# Lora_Node.net
KiCad netlist of a schematic drawn in EAGLE
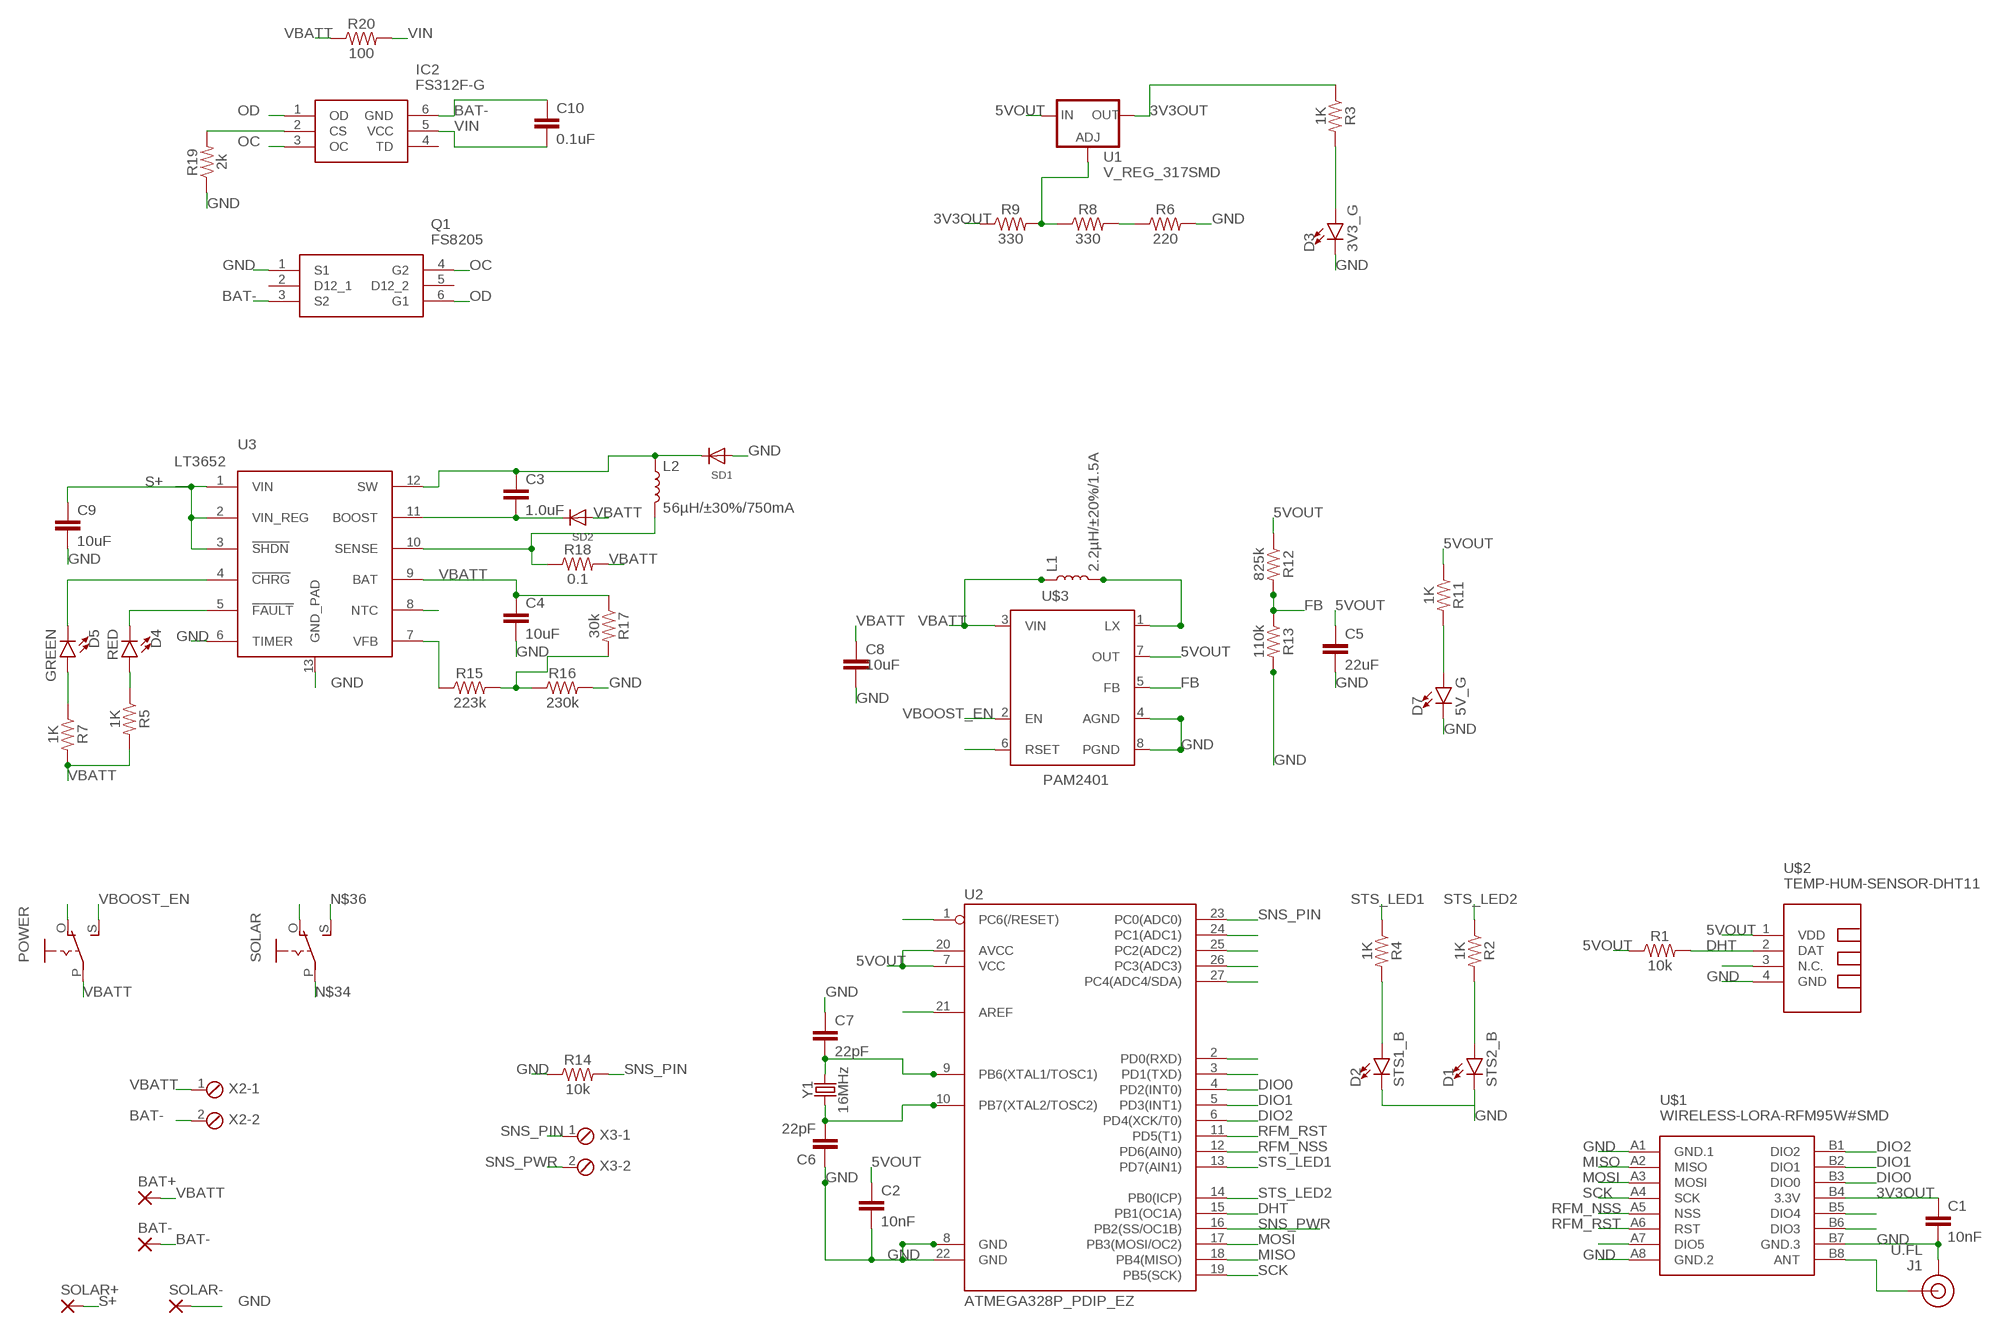
[diagram p0: schematic, sheet 1]

(export (version "E")
  (design (tool "Eeschema 10.0.6"))
  (components
    (comp (ref "BAT+")
      (value "SMD5")
      (footprint "eagle-import:SMD2,54-5,08")
      (libsource (lib "eagle-import") (part "SMD5"))
    )
    (comp (ref "BAT-")
      (value "SMD5")
      (footprint "eagle-import:SMD2,54-5,08")
      (libsource (lib "eagle-import") (part "SMD5"))
    )
    (comp (ref "C1")
      (value "10nF")
      (footprint "eagle-import:0603")
      (libsource (lib "eagle-import") (part "10NF-0603-50V-10%"))
    )
    (comp (ref "C2")
      (value "10nF")
      (footprint "eagle-import:0603")
      (libsource (lib "eagle-import") (part "10NF-0603-50V-10%"))
    )
    (comp (ref "C3")
      (value "1.0uF")
      (footprint "eagle-import:0805")
      (libsource (lib "eagle-import") (part "1.0UF-0805-25V-(+80/-20%)"))
    )
    (comp (ref "C4")
      (value "10uF")
      (footprint "eagle-import:0805")
      (libsource (lib "eagle-import") (part "10UF-0805-10V-10%"))
    )
    (comp (ref "C5")
      (value "22uF")
      (footprint "eagle-import:0805")
      (libsource (lib "eagle-import") (part "22UF-0805-6.3V-20%"))
    )
    (comp (ref "C6")
      (value "22pF")
      (footprint "eagle-import:0603")
      (libsource (lib "eagle-import") (part "22PF-0603-50V-5%"))
    )
    (comp (ref "C7")
      (value "22pF")
      (footprint "eagle-import:0603")
      (libsource (lib "eagle-import") (part "22PF-0603-50V-5%"))
    )
    (comp (ref "C8")
      (value "10uF")
      (footprint "eagle-import:0805")
      (libsource (lib "eagle-import") (part "10UF-0805-10V-10%"))
    )
    (comp (ref "C9")
      (value "10uF")
      (footprint "eagle-import:1210")
      (libsource (lib "eagle-import") (part "10UF-1210-50V-20%"))
    )
    (comp (ref "C10")
      (value "0.1uF")
      (footprint "eagle-import:0603")
      (libsource (lib "eagle-import") (part "0.1UF-0603-25V-5%"))
    )
    (comp (ref "D1")
      (value "STS2_B")
      (footprint "eagle-import:LED-1206")
      (libsource (lib "eagle-import") (part "LED-BLUE1206"))
    )
    (comp (ref "D2")
      (value "STS1_B")
      (footprint "eagle-import:LED-1206")
      (libsource (lib "eagle-import") (part "LED-BLUE1206"))
    )
    (comp (ref "D3")
      (value "3V3_G")
      (footprint "eagle-import:LED-0603")
      (libsource (lib "eagle-import") (part "LED-GREEN0603"))
    )
    (comp (ref "D4")
      (value "RED")
      (footprint "eagle-import:LED-0603")
      (libsource (lib "eagle-import") (part "LED-RED0603"))
    )
    (comp (ref "D5")
      (value "GREEN")
      (footprint "eagle-import:LED-0603")
      (libsource (lib "eagle-import") (part "LED-GREEN0603"))
    )
    (comp (ref "D7")
      (value "5V_G")
      (footprint "eagle-import:LED-0603")
      (libsource (lib "eagle-import") (part "LED-GREEN0603"))
    )
    (comp (ref "IC2")
      (value "FS312F-G")
      (footprint "eagle-import:SOT95P280X145-6N")
      (libsource (lib "eagle-import") (part "FS312F-G"))
    )
    (comp (ref "J1")
      (value "U.FL")
      (footprint "eagle-import:U.FL")
      (libsource (lib "eagle-import") (part "U.FL2PIN"))
    )
    (comp (ref "L1")
      (value "2.2µH/±20%/1.5A")
      (footprint "eagle-import:INDUCTOR_2.2UH")
      (libsource (lib "eagle-import") (part "INDUCTOR-VLF4012AT-2.2UH"))
    )
    (comp (ref "L2")
      (value "56µH/±30%/750mA")
      (footprint "eagle-import:CR54")
      (libsource (lib "eagle-import") (part "INDUCTOR-CR54-47UH"))
    )
    (comp (ref "POWER")
      (value "EG1218S")
      (footprint "eagle-import:EG1218")
      (libsource (lib "eagle-import") (part "EG1218S"))
    )
    (comp (ref "Q1")
      (value "FS8205")
      (footprint "eagle-import:FS8205")
      (libsource (lib "eagle-import") (part "FS8205"))
    )
    (comp (ref "R1")
      (value "10k")
      (footprint "eagle-import:0603")
      (libsource (lib "eagle-import") (part "10KOHM-0603-1/10W-1%"))
    )
    (comp (ref "R2")
      (value "1K")
      (footprint "eagle-import:0603")
      (libsource (lib "eagle-import") (part "220OHM-0603-1/10W-1%"))
    )
    (comp (ref "R3")
      (value "1K")
      (footprint "eagle-import:0603")
      (libsource (lib "eagle-import") (part "220OHM-0603-1/10W-1%"))
    )
    (comp (ref "R4")
      (value "1K")
      (footprint "eagle-import:0603")
      (libsource (lib "eagle-import") (part "220OHM-0603-1/10W-1%"))
    )
    (comp (ref "R5")
      (value "1K")
      (footprint "eagle-import:0603")
      (libsource (lib "eagle-import") (part "220OHM-0603-1/10W-1%"))
    )
    (comp (ref "R6")
      (value "220")
      (footprint "eagle-import:0603")
      (libsource (lib "eagle-import") (part "220OHM-0603-1/10W-1%"))
    )
    (comp (ref "R7")
      (value "1K")
      (footprint "eagle-import:0603")
      (libsource (lib "eagle-import") (part "220OHM-0603-1/10W-1%"))
    )
    (comp (ref "R8")
      (value "330")
      (footprint "eagle-import:0603")
      (libsource (lib "eagle-import") (part "330OHM-0603-1/10W-1%"))
    )
    (comp (ref "R9")
      (value "330")
      (footprint "eagle-import:0603")
      (libsource (lib "eagle-import") (part "330OHM-0603-1/10W-1%"))
    )
    (comp (ref "R11")
      (value "1K")
      (footprint "eagle-import:0603")
      (libsource (lib "eagle-import") (part "220OHM-0603-1/10W-1%"))
    )
    (comp (ref "R12")
      (value "825k")
      (footprint "eagle-import:0603")
      (libsource (lib "eagle-import") (part "820KOHM-0603-1/10W-1%"))
    )
    (comp (ref "R13")
      (value "110k")
      (footprint "eagle-import:0603")
      (libsource (lib "eagle-import") (part "100KOHM-0603-1/10W-1%"))
    )
    (comp (ref "R14")
      (value "10k")
      (footprint "eagle-import:0603")
      (libsource (lib "eagle-import") (part "10KOHM-0603-1/10W-1%"))
    )
    (comp (ref "R15")
      (value "223k")
      (footprint "eagle-import:0603")
      (libsource (lib "eagle-import") (part "220KOHM-0603-1/10W-1%"))
    )
    (comp (ref "R16")
      (value "230k")
      (footprint "eagle-import:0603")
      (libsource (lib "eagle-import") (part "220KOHM-0603-1/10W-1%"))
    )
    (comp (ref "R17")
      (value "30k")
      (footprint "eagle-import:0603")
      (libsource (lib "eagle-import") (part "30.1KOHM-0603-1/10W-1%"))
    )
    (comp (ref "R18")
      (value "0.1")
      (footprint "eagle-import:1210")
      (libsource (lib "eagle-import") (part "0.1OHM-1210-1/2W-1%"))
    )
    (comp (ref "R19")
      (value "2k")
      (footprint "eagle-import:0603")
      (libsource (lib "eagle-import") (part "220KOHM-0603-1/10W-1%"))
    )
    (comp (ref "R20")
      (value "100")
      (footprint "eagle-import:0603")
      (libsource (lib "eagle-import") (part "100OHM-0603-1/4W-5%"))
    )
    (comp (ref "SD1")
      (value "DIODESMA")
      (footprint "eagle-import:SMADIODE")
      (libsource (lib "eagle-import") (part "DIODESMA"))
    )
    (comp (ref "SD2")
      (value "DIODESMA")
      (footprint "eagle-import:SMADIODE")
      (libsource (lib "eagle-import") (part "DIODESMA"))
    )
    (comp (ref "SOLAR")
      (value "EG1218S")
      (footprint "eagle-import:EG1218")
      (libsource (lib "eagle-import") (part "EG1218S"))
    )
    (comp (ref "SOLAR+")
      (value "SMD5")
      (footprint "eagle-import:SMD2,54-5,08")
      (libsource (lib "eagle-import") (part "SMD5"))
    )
    (comp (ref "SOLAR-")
      (value "SMD5")
      (footprint "eagle-import:SMD2,54-5,08")
      (libsource (lib "eagle-import") (part "SMD5"))
    )
    (comp (ref "U$1")
      (value "WIRELESS-LORA-RFM95W#SMD")
      (footprint "eagle-import:WIRELESS-LORA-RFM95W#SMD")
      (libsource (lib "eagle-import") (part "WIRELESS-LORA-RFM95W#SMD"))
    )
    (comp (ref "U$2")
      (value "TEMP-HUM-SENSOR-DHT11")
      (footprint "eagle-import:TEMP-HUM-SENSOR-DHT11")
      (libsource (lib "eagle-import") (part "TEMP-HUM-SENSOR-DHT11"))
    )
    (comp (ref "U$3")
      (value "PAM2401")
      (footprint "eagle-import:MSOP8")
      (libsource (lib "eagle-import") (part "PAM2401"))
    )
    (comp (ref "U1")
      (value "V_REG_317SMD")
      (footprint "eagle-import:SOT223")
      (libsource (lib "eagle-import") (part "V_REG_317SMD"))
    )
    (comp (ref "U2")
      (value "ATMEGA328P_PDIP_EZ")
      (footprint "eagle-import:DIP28-SIMON-KIT")
      (libsource (lib "eagle-import") (part "ATMEGA328P_PDIP_EZ"))
    )
    (comp (ref "U3")
      (value "LT3652")
      (footprint "eagle-import:MSOP-12_GND")
      (libsource (lib "eagle-import") (part "LT3652"))
    )
    (comp (ref "X2")
      (value "MPT2")
      (footprint "eagle-import:2POL254")
      (libsource (lib "eagle-import") (part "MPT2"))
    )
    (comp (ref "X3")
      (value "MPT2")
      (footprint "eagle-import:2POL254")
      (libsource (lib "eagle-import") (part "MPT2"))
    )
    (comp (ref "Y1")
      (value "16MHz")
      (footprint "eagle-import:HC49US")
      (libsource (lib "eagle-import") (part "CRYSTAL-16MHZPTH-HC49US"))
    )
  )
  (nets
    (net (code "1") (name "/3V3OUT") (class "Default")
      (node (ref "C1") (pin "1") (pinfunction "1_1") (pintype "passive"))
      (node (ref "R3") (pin "1") (pinfunction "1_1") (pintype "passive"))
      (node (ref "R9") (pin "1") (pinfunction "1_1") (pintype "passive"))
      (node (ref "U$1") (pin "B4") (pinfunction "3.3V_B4") (pintype "power_in"))
      (node (ref "U1") (pin "2") (pinfunction "OUT_2") (pintype "output"))
    )
    (net (code "2") (name "/5VOUT") (class "Default")
      (node (ref "C2") (pin "1") (pinfunction "1_1") (pintype "passive"))
      (node (ref "C5") (pin "1") (pinfunction "1_1") (pintype "passive"))
      (node (ref "R1") (pin "1") (pinfunction "1_1") (pintype "passive"))
      (node (ref "R11") (pin "1") (pinfunction "1_1") (pintype "passive"))
      (node (ref "R12") (pin "1") (pinfunction "1_1") (pintype "passive"))
      (node (ref "U$2") (pin "1") (pinfunction "VDD_1") (pintype "power_in"))
      (node (ref "U$3") (pin "7") (pinfunction "OUT_7") (pintype "bidirectional"))
      (node (ref "U1") (pin "3") (pinfunction "IN_3") (pintype "input"))
      (node (ref "U2") (pin "20") (pinfunction "AVCC_20") (pintype "bidirectional"))
      (node (ref "U2") (pin "7") (pinfunction "VCC_7") (pintype "bidirectional"))
    )
    (net (code "3") (name "/BAT-") (class "Default")
      (node (ref "BAT-") (pin "1") (pinfunction "P_1") (pintype "passive"))
      (node (ref "C10") (pin "1") (pinfunction "1_1") (pintype "passive"))
      (node (ref "IC2") (pin "6") (pinfunction "GND_6") (pintype "bidirectional"))
      (node (ref "Q1") (pin "3") (pinfunction "S2_3") (pintype "bidirectional"))
      (node (ref "X2") (pin "2") (pinfunction "1_2") (pintype "passive"))
    )
    (net (code "4") (name "/DHT") (class "Default")
      (node (ref "R1") (pin "2") (pinfunction "2_2") (pintype "passive"))
      (node (ref "U$2") (pin "2") (pinfunction "DAT_2") (pintype "bidirectional"))
      (node (ref "U2") (pin "15") (pinfunction "PB1(OC1A)_15") (pintype "bidirectional"))
    )
    (net (code "5") (name "/DIO0") (class "Default")
      (node (ref "U$1") (pin "B3") (pinfunction "DIO0_B3") (pintype "bidirectional"))
      (node (ref "U2") (pin "4") (pinfunction "PD2(INT0)_4") (pintype "bidirectional"))
    )
    (net (code "6") (name "/DIO1") (class "Default")
      (node (ref "U$1") (pin "B2") (pinfunction "DIO1_B2") (pintype "bidirectional"))
      (node (ref "U2") (pin "5") (pinfunction "PD3(INT1)_5") (pintype "bidirectional"))
    )
    (net (code "7") (name "/DIO2") (class "Default")
      (node (ref "U$1") (pin "B1") (pinfunction "DIO2_B1") (pintype "bidirectional"))
      (node (ref "U2") (pin "6") (pinfunction "PD4(XCK/T0)_6") (pintype "bidirectional"))
    )
    (net (code "8") (name "/FB") (class "Default")
      (node (ref "R12") (pin "2") (pinfunction "2_2") (pintype "passive"))
      (node (ref "R13") (pin "1") (pinfunction "1_1") (pintype "passive"))
      (node (ref "U$3") (pin "5") (pinfunction "FB_5") (pintype "bidirectional"))
    )
    (net (code "9") (name "/GND") (class "Default")
      (node (ref "C1") (pin "2") (pinfunction "2_2") (pintype "passive"))
      (node (ref "C2") (pin "2") (pinfunction "2_2") (pintype "passive"))
      (node (ref "C4") (pin "2") (pinfunction "2_2") (pintype "passive"))
      (node (ref "C5") (pin "2") (pinfunction "2_2") (pintype "passive"))
      (node (ref "C6") (pin "1") (pinfunction "1_1") (pintype "passive"))
      (node (ref "C7") (pin "1") (pinfunction "1_1") (pintype "passive"))
      (node (ref "C8") (pin "2") (pinfunction "2_2") (pintype "passive"))
      (node (ref "C9") (pin "2") (pinfunction "2_2") (pintype "passive"))
      (node (ref "D1") (pin "C") (pinfunction "C_C") (pintype "passive"))
      (node (ref "D2") (pin "C") (pinfunction "C_C") (pintype "passive"))
      (node (ref "D3") (pin "C") (pinfunction "C_C") (pintype "passive"))
      (node (ref "D7") (pin "C") (pinfunction "C_C") (pintype "passive"))
      (node (ref "J1") (pin "1") (pinfunction "GND_1") (pintype "bidirectional"))
      (node (ref "J1") (pin "2") (pinfunction "GND_2") (pintype "bidirectional"))
      (node (ref "Q1") (pin "1") (pinfunction "S1_1") (pintype "bidirectional"))
      (node (ref "R13") (pin "2") (pinfunction "2_2") (pintype "passive"))
      (node (ref "R14") (pin "1") (pinfunction "1_1") (pintype "passive"))
      (node (ref "R16") (pin "2") (pinfunction "2_2") (pintype "passive"))
      (node (ref "R19") (pin "1") (pinfunction "1_1") (pintype "passive"))
      (node (ref "R6") (pin "2") (pinfunction "2_2") (pintype "passive"))
      (node (ref "SD1") (pin "A") (pinfunction "A_A") (pintype "passive"))
      (node (ref "SOLAR-") (pin "1") (pinfunction "P_1") (pintype "passive"))
      (node (ref "U$1") (pin "A1") (pinfunction "GND.1_A1") (pintype "power_in"))
      (node (ref "U$1") (pin "A8") (pinfunction "GND.2_A8") (pintype "power_in"))
      (node (ref "U$1") (pin "B7") (pinfunction "GND.3_B7") (pintype "power_in"))
      (node (ref "U$2") (pin "4") (pinfunction "GND_4") (pintype "power_in"))
      (node (ref "U$3") (pin "4") (pinfunction "AGND_4") (pintype "bidirectional"))
      (node (ref "U$3") (pin "8") (pinfunction "PGND_8") (pintype "bidirectional"))
      (node (ref "U2") (pin "22") (pinfunction "GND_22") (pintype "bidirectional"))
      (node (ref "U2") (pin "8") (pinfunction "GND_8") (pintype "bidirectional"))
      (node (ref "U3") (pin "13") (pinfunction "GND_PAD_13") (pintype "bidirectional"))
      (node (ref "U3") (pin "6") (pinfunction "TIMER_6") (pintype "bidirectional"))
    )
    (net (code "10") (name "/MISO") (class "Default")
      (node (ref "U$1") (pin "A2") (pinfunction "MISO_A2") (pintype "bidirectional"))
      (node (ref "U2") (pin "18") (pinfunction "PB4(MISO)_18") (pintype "bidirectional"))
    )
    (net (code "11") (name "/MOSI") (class "Default")
      (node (ref "U$1") (pin "A3") (pinfunction "MOSI_A3") (pintype "bidirectional"))
      (node (ref "U2") (pin "17") (pinfunction "PB3(MOSI/OC2)_17") (pintype "bidirectional"))
    )
    (net (code "12") (name "/N$34") (class "Default")
      (node (ref "SOLAR") (pin "P") (pinfunction "P_P") (pintype "passive"))
    )
    (net (code "13") (name "/N$36") (class "Default")
      (node (ref "SOLAR") (pin "S") (pinfunction "S_S") (pintype "passive"))
    )
    (net (code "14") (name "/OC") (class "Default")
      (node (ref "IC2") (pin "3") (pinfunction "OC_3") (pintype "bidirectional"))
      (node (ref "Q1") (pin "4") (pinfunction "G2_4") (pintype "bidirectional"))
    )
    (net (code "15") (name "/OD") (class "Default")
      (node (ref "IC2") (pin "1") (pinfunction "OD_1") (pintype "bidirectional"))
      (node (ref "Q1") (pin "6") (pinfunction "G1_6") (pintype "bidirectional"))
    )
    (net (code "16") (name "/RFM_NSS") (class "Default")
      (node (ref "U$1") (pin "A5") (pinfunction "NSS_A5") (pintype "bidirectional"))
      (node (ref "U2") (pin "12") (pinfunction "PD6(AIN0)_12") (pintype "bidirectional"))
    )
    (net (code "17") (name "/RFM_RST") (class "Default")
      (node (ref "U$1") (pin "A6") (pinfunction "RST_A6") (pintype "bidirectional"))
      (node (ref "U2") (pin "11") (pinfunction "PD5(T1)_11") (pintype "bidirectional"))
    )
    (net (code "18") (name "/S+") (class "Default")
      (node (ref "C9") (pin "1") (pinfunction "1_1") (pintype "passive"))
      (node (ref "SOLAR+") (pin "1") (pinfunction "P_1") (pintype "passive"))
      (node (ref "U3") (pin "1") (pinfunction "VIN_1") (pintype "bidirectional"))
      (node (ref "U3") (pin "2") (pinfunction "VIN_REG_2") (pintype "bidirectional"))
      (node (ref "U3") (pin "3") (pinfunction "~{SHDN}_3") (pintype "bidirectional"))
    )
    (net (code "19") (name "/SCK") (class "Default")
      (node (ref "U$1") (pin "A4") (pinfunction "SCK_A4") (pintype "bidirectional"))
      (node (ref "U2") (pin "19") (pinfunction "PB5(SCK)_19") (pintype "bidirectional"))
    )
    (net (code "20") (name "/SNS_PIN") (class "Default")
      (node (ref "R14") (pin "2") (pinfunction "2_2") (pintype "passive"))
      (node (ref "U2") (pin "23") (pinfunction "PC0(ADC0)_23") (pintype "bidirectional"))
      (node (ref "X3") (pin "1") (pinfunction "1_1") (pintype "passive"))
    )
    (net (code "21") (name "/SNS_PWR") (class "Default")
      (node (ref "U2") (pin "16") (pinfunction "PB2(SS/OC1B)_16") (pintype "bidirectional"))
      (node (ref "X3") (pin "2") (pinfunction "1_2") (pintype "passive"))
    )
    (net (code "22") (name "/STS_LED1") (class "Default")
      (node (ref "R4") (pin "1") (pinfunction "1_1") (pintype "passive"))
      (node (ref "U2") (pin "13") (pinfunction "PD7(AIN1)_13") (pintype "bidirectional"))
    )
    (net (code "23") (name "/STS_LED2") (class "Default")
      (node (ref "R2") (pin "1") (pinfunction "1_1") (pintype "passive"))
      (node (ref "U2") (pin "14") (pinfunction "PB0(ICP)_14") (pintype "bidirectional"))
    )
    (net (code "24") (name "/VBATT") (class "Default")
      (node (ref "BAT+") (pin "1") (pinfunction "P_1") (pintype "passive"))
      (node (ref "C4") (pin "1") (pinfunction "1_1") (pintype "passive"))
      (node (ref "C8") (pin "1") (pinfunction "1_1") (pintype "passive"))
      (node (ref "L1") (pin "P$1") (pinfunction "1_P$1") (pintype "passive"))
      (node (ref "POWER") (pin "P") (pinfunction "P_P") (pintype "passive"))
      (node (ref "R17") (pin "1") (pinfunction "1_1") (pintype "passive"))
      (node (ref "R18") (pin "2") (pinfunction "2_2") (pintype "passive"))
      (node (ref "R20") (pin "1") (pinfunction "1_1") (pintype "passive"))
      (node (ref "R5") (pin "2") (pinfunction "2_2") (pintype "passive"))
      (node (ref "R7") (pin "2") (pinfunction "2_2") (pintype "passive"))
      (node (ref "SD2") (pin "A") (pinfunction "A_A") (pintype "passive"))
      (node (ref "U$3") (pin "3") (pinfunction "VIN_3") (pintype "bidirectional"))
      (node (ref "U3") (pin "9") (pinfunction "BAT_9") (pintype "bidirectional"))
      (node (ref "X2") (pin "1") (pinfunction "1_1") (pintype "passive"))
    )
    (net (code "25") (name "/VBOOST_EN") (class "Default")
      (node (ref "POWER") (pin "S") (pinfunction "S_S") (pintype "passive"))
      (node (ref "U$3") (pin "2") (pinfunction "EN_2") (pintype "bidirectional"))
    )
    (net (code "26") (name "/VIN") (class "Default")
      (node (ref "C10") (pin "2") (pinfunction "2_2") (pintype "passive"))
      (node (ref "IC2") (pin "5") (pinfunction "VCC_5") (pintype "bidirectional"))
      (node (ref "R20") (pin "2") (pinfunction "2_2") (pintype "passive"))
    )
    (net (code "27") (name "Net-(D1-PadA)") (class "Default")
      (node (ref "D1") (pin "A") (pinfunction "A_A") (pintype "passive"))
      (node (ref "R2") (pin "2") (pinfunction "2_2") (pintype "passive"))
    )
    (net (code "28") (name "Net-(D2-PadA)") (class "Default")
      (node (ref "D2") (pin "A") (pinfunction "A_A") (pintype "passive"))
      (node (ref "R4") (pin "2") (pinfunction "2_2") (pintype "passive"))
    )
    (net (code "29") (name "Net-(D3-PadA)") (class "Default")
      (node (ref "D3") (pin "A") (pinfunction "A_A") (pintype "passive"))
      (node (ref "R3") (pin "2") (pinfunction "2_2") (pintype "passive"))
    )
    (net (code "30") (name "Net-(D4-PadA)") (class "Default")
      (node (ref "D4") (pin "A") (pinfunction "A_A") (pintype "passive"))
      (node (ref "R5") (pin "1") (pinfunction "1_1") (pintype "passive"))
    )
    (net (code "31") (name "Net-(D5-PadA)") (class "Default")
      (node (ref "D5") (pin "A") (pinfunction "A_A") (pintype "passive"))
      (node (ref "R7") (pin "1") (pinfunction "1_1") (pintype "passive"))
    )
    (net (code "32") (name "Net-(D7-PadA)") (class "Default")
      (node (ref "D7") (pin "A") (pinfunction "A_A") (pintype "passive"))
      (node (ref "R11") (pin "2") (pinfunction "2_2") (pintype "passive"))
    )
    (net (code "33") (name "Net-(IC2-CS)") (class "Default")
      (node (ref "IC2") (pin "2") (pinfunction "CS_2") (pintype "bidirectional"))
      (node (ref "R19") (pin "2") (pinfunction "2_2") (pintype "passive"))
    )
    (net (code "34") (name "Net-(J1-SIGNAL)") (class "Default")
      (node (ref "J1") (pin "FEED") (pinfunction "SIGNAL_FEED") (pintype "bidirectional"))
      (node (ref "U$1") (pin "B8") (pinfunction "ANT_B8") (pintype "passive"))
    )
    (net (code "35") (name "Net-(L1-2)") (class "Default")
      (node (ref "L1") (pin "P$2") (pinfunction "2_P$2") (pintype "passive"))
      (node (ref "U$3") (pin "1") (pinfunction "LX_1") (pintype "bidirectional"))
    )
    (net (code "36") (name "Net-(L2-1)") (class "Default")
      (node (ref "C3") (pin "1") (pinfunction "1_1") (pintype "passive"))
      (node (ref "L2") (pin "P$1") (pinfunction "1_P$1") (pintype "passive"))
      (node (ref "SD1") (pin "C") (pinfunction "C_C") (pintype "passive"))
      (node (ref "U3") (pin "12") (pinfunction "SW_12") (pintype "bidirectional"))
    )
    (net (code "37") (name "Net-(L2-2)") (class "Default")
      (node (ref "L2") (pin "P$2") (pinfunction "2_P$2") (pintype "passive"))
      (node (ref "R18") (pin "1") (pinfunction "1_1") (pintype "passive"))
      (node (ref "U3") (pin "10") (pinfunction "SENSE_10") (pintype "bidirectional"))
    )
    (net (code "38") (name "Net-(R6-Pad1)") (class "Default")
      (node (ref "R6") (pin "1") (pinfunction "1_1") (pintype "passive"))
      (node (ref "R8") (pin "2") (pinfunction "2_2") (pintype "passive"))
    )
    (net (code "39") (name "Net-(R15-Pad2)") (class "Default")
      (node (ref "R15") (pin "2") (pinfunction "2_2") (pintype "passive"))
      (node (ref "R16") (pin "1") (pinfunction "1_1") (pintype "passive"))
      (node (ref "R17") (pin "2") (pinfunction "2_2") (pintype "passive"))
    )
    (net (code "40") (name "Net-(U1-ADJ)") (class "Default")
      (node (ref "R8") (pin "1") (pinfunction "1_1") (pintype "passive"))
      (node (ref "R9") (pin "2") (pinfunction "2_2") (pintype "passive"))
      (node (ref "U1") (pin "1") (pinfunction "ADJ_1") (pintype "input"))
    )
    (net (code "41") (name "Net-(U2-PB6(XTAL1{slash}TOSC1))") (class "Default")
      (node (ref "C7") (pin "2") (pinfunction "2_2") (pintype "passive"))
      (node (ref "U2") (pin "9") (pinfunction "PB6(XTAL1/TOSC1)_9") (pintype "bidirectional"))
      (node (ref "Y1") (pin "2") (pinfunction "2_2") (pintype "passive"))
    )
    (net (code "42") (name "Net-(U2-PB7(XTAL2{slash}TOSC2))") (class "Default")
      (node (ref "C6") (pin "2") (pinfunction "2_2") (pintype "passive"))
      (node (ref "U2") (pin "10") (pinfunction "PB7(XTAL2/TOSC2)_10") (pintype "bidirectional"))
      (node (ref "Y1") (pin "1") (pinfunction "1_1") (pintype "passive"))
    )
    (net (code "43") (name "Net-(U3-BOOST)") (class "Default")
      (node (ref "C3") (pin "2") (pinfunction "2_2") (pintype "passive"))
      (node (ref "SD2") (pin "C") (pinfunction "C_C") (pintype "passive"))
      (node (ref "U3") (pin "11") (pinfunction "BOOST_11") (pintype "bidirectional"))
    )
    (net (code "44") (name "Net-(U3-VFB)") (class "Default")
      (node (ref "R15") (pin "1") (pinfunction "1_1") (pintype "passive"))
      (node (ref "U3") (pin "7") (pinfunction "VFB_7") (pintype "bidirectional"))
    )
    (net (code "45") (name "Net-(U3-~{CHRG})") (class "Default")
      (node (ref "D5") (pin "C") (pinfunction "C_C") (pintype "passive"))
      (node (ref "U3") (pin "4") (pinfunction "~{CHRG}_4") (pintype "bidirectional"))
    )
    (net (code "46") (name "Net-(U3-~{FAULT})") (class "Default")
      (node (ref "D4") (pin "C") (pinfunction "C_C") (pintype "passive"))
      (node (ref "U3") (pin "5") (pinfunction "~{FAULT}_5") (pintype "bidirectional"))
    )
    (net (code "47") (name "unconnected-(IC2-TD-Pad4)") (class "Default")
      (node (ref "IC2") (pin "4") (pinfunction "TD_4") (pintype "bidirectional"))
    )
    (net (code "48") (name "unconnected-(POWER-PadO)") (class "Default")
      (node (ref "POWER") (pin "O") (pinfunction "O_O") (pintype "passive"))
    )
    (net (code "49") (name "unconnected-(Q1-D12_1-Pad2)") (class "Default")
      (node (ref "Q1") (pin "2") (pinfunction "D12_1_2") (pintype "bidirectional"))
    )
    (net (code "50") (name "unconnected-(Q1-D12_2-Pad5)") (class "Default")
      (node (ref "Q1") (pin "5") (pinfunction "D12_2_5") (pintype "bidirectional"))
    )
    (net (code "51") (name "unconnected-(SOLAR-PadO)") (class "Default")
      (node (ref "SOLAR") (pin "O") (pinfunction "O_O") (pintype "passive"))
    )
    (net (code "52") (name "unconnected-(U$1-DIO3-PadB6)") (class "Default")
      (node (ref "U$1") (pin "B6") (pinfunction "DIO3_B6") (pintype "bidirectional"))
    )
    (net (code "53") (name "unconnected-(U$1-DIO4-PadB5)") (class "Default")
      (node (ref "U$1") (pin "B5") (pinfunction "DIO4_B5") (pintype "bidirectional"))
    )
    (net (code "54") (name "unconnected-(U$1-DIO5-PadA7)") (class "Default")
      (node (ref "U$1") (pin "A7") (pinfunction "DIO5_A7") (pintype "bidirectional"))
    )
    (net (code "55") (name "unconnected-(U$2-N.C.-Pad3)") (class "Default")
      (node (ref "U$2") (pin "3") (pinfunction "N.C._3") (pintype "passive"))
    )
    (net (code "56") (name "unconnected-(U$3-RSET-Pad6)") (class "Default")
      (node (ref "U$3") (pin "6") (pinfunction "RSET_6") (pintype "bidirectional"))
    )
    (net (code "57") (name "unconnected-(U2-AREF-Pad21)") (class "Default")
      (node (ref "U2") (pin "21") (pinfunction "AREF_21") (pintype "bidirectional"))
    )
    (net (code "58") (name "unconnected-(U2-PC1(ADC1)-Pad24)") (class "Default")
      (node (ref "U2") (pin "24") (pinfunction "PC1(ADC1)_24") (pintype "bidirectional"))
    )
    (net (code "59") (name "unconnected-(U2-PC2(ADC2)-Pad25)") (class "Default")
      (node (ref "U2") (pin "25") (pinfunction "PC2(ADC2)_25") (pintype "bidirectional"))
    )
    (net (code "60") (name "unconnected-(U2-PC3(ADC3)-Pad26)") (class "Default")
      (node (ref "U2") (pin "26") (pinfunction "PC3(ADC3)_26") (pintype "bidirectional"))
    )
    (net (code "61") (name "unconnected-(U2-PC4(ADC4{slash}SDA)-Pad27)") (class "Default")
      (node (ref "U2") (pin "27") (pinfunction "PC4(ADC4/SDA)_27") (pintype "bidirectional"))
    )
    (net (code "62") (name "unconnected-(U2-PC6({slash}RESET)-Pad1)") (class "Default")
      (node (ref "U2") (pin "1") (pinfunction "PC6(/RESET)_1") (pintype "bidirectional"))
    )
    (net (code "63") (name "unconnected-(U2-PD0(RXD)-Pad2)") (class "Default")
      (node (ref "U2") (pin "2") (pinfunction "PD0(RXD)_2") (pintype "bidirectional"))
    )
    (net (code "64") (name "unconnected-(U2-PD1(TXD)-Pad3)") (class "Default")
      (node (ref "U2") (pin "3") (pinfunction "PD1(TXD)_3") (pintype "bidirectional"))
    )
    (net (code "65") (name "unconnected-(U3-NTC-Pad8)") (class "Default")
      (node (ref "U3") (pin "8") (pinfunction "NTC_8") (pintype "bidirectional"))
    )
  )
)
